# V1c_pcb.net
KiCad netlist of a schematic drawn in EAGLE
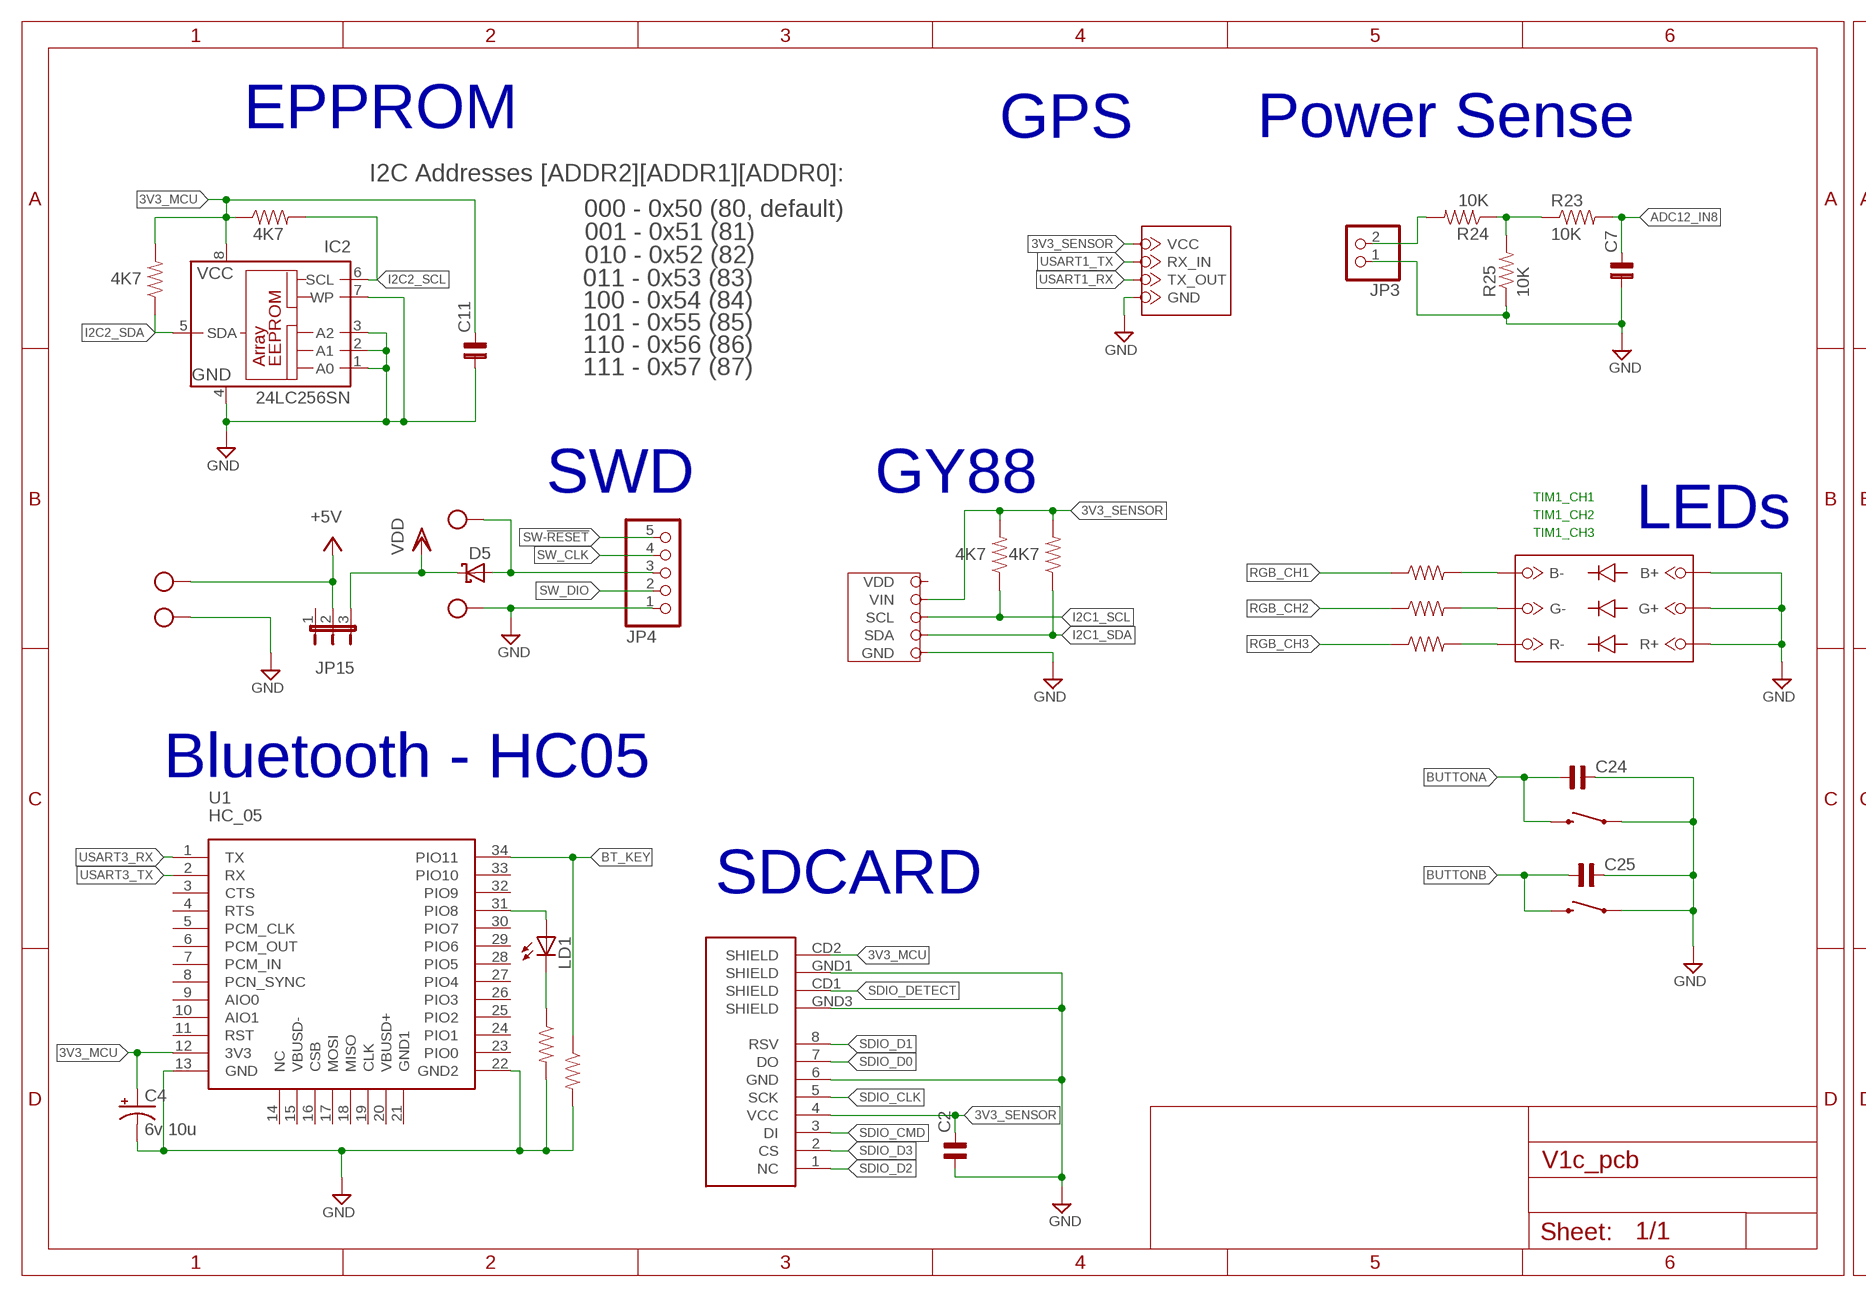
[diagram p0: schematic, sheet 1, part 1 of 2]
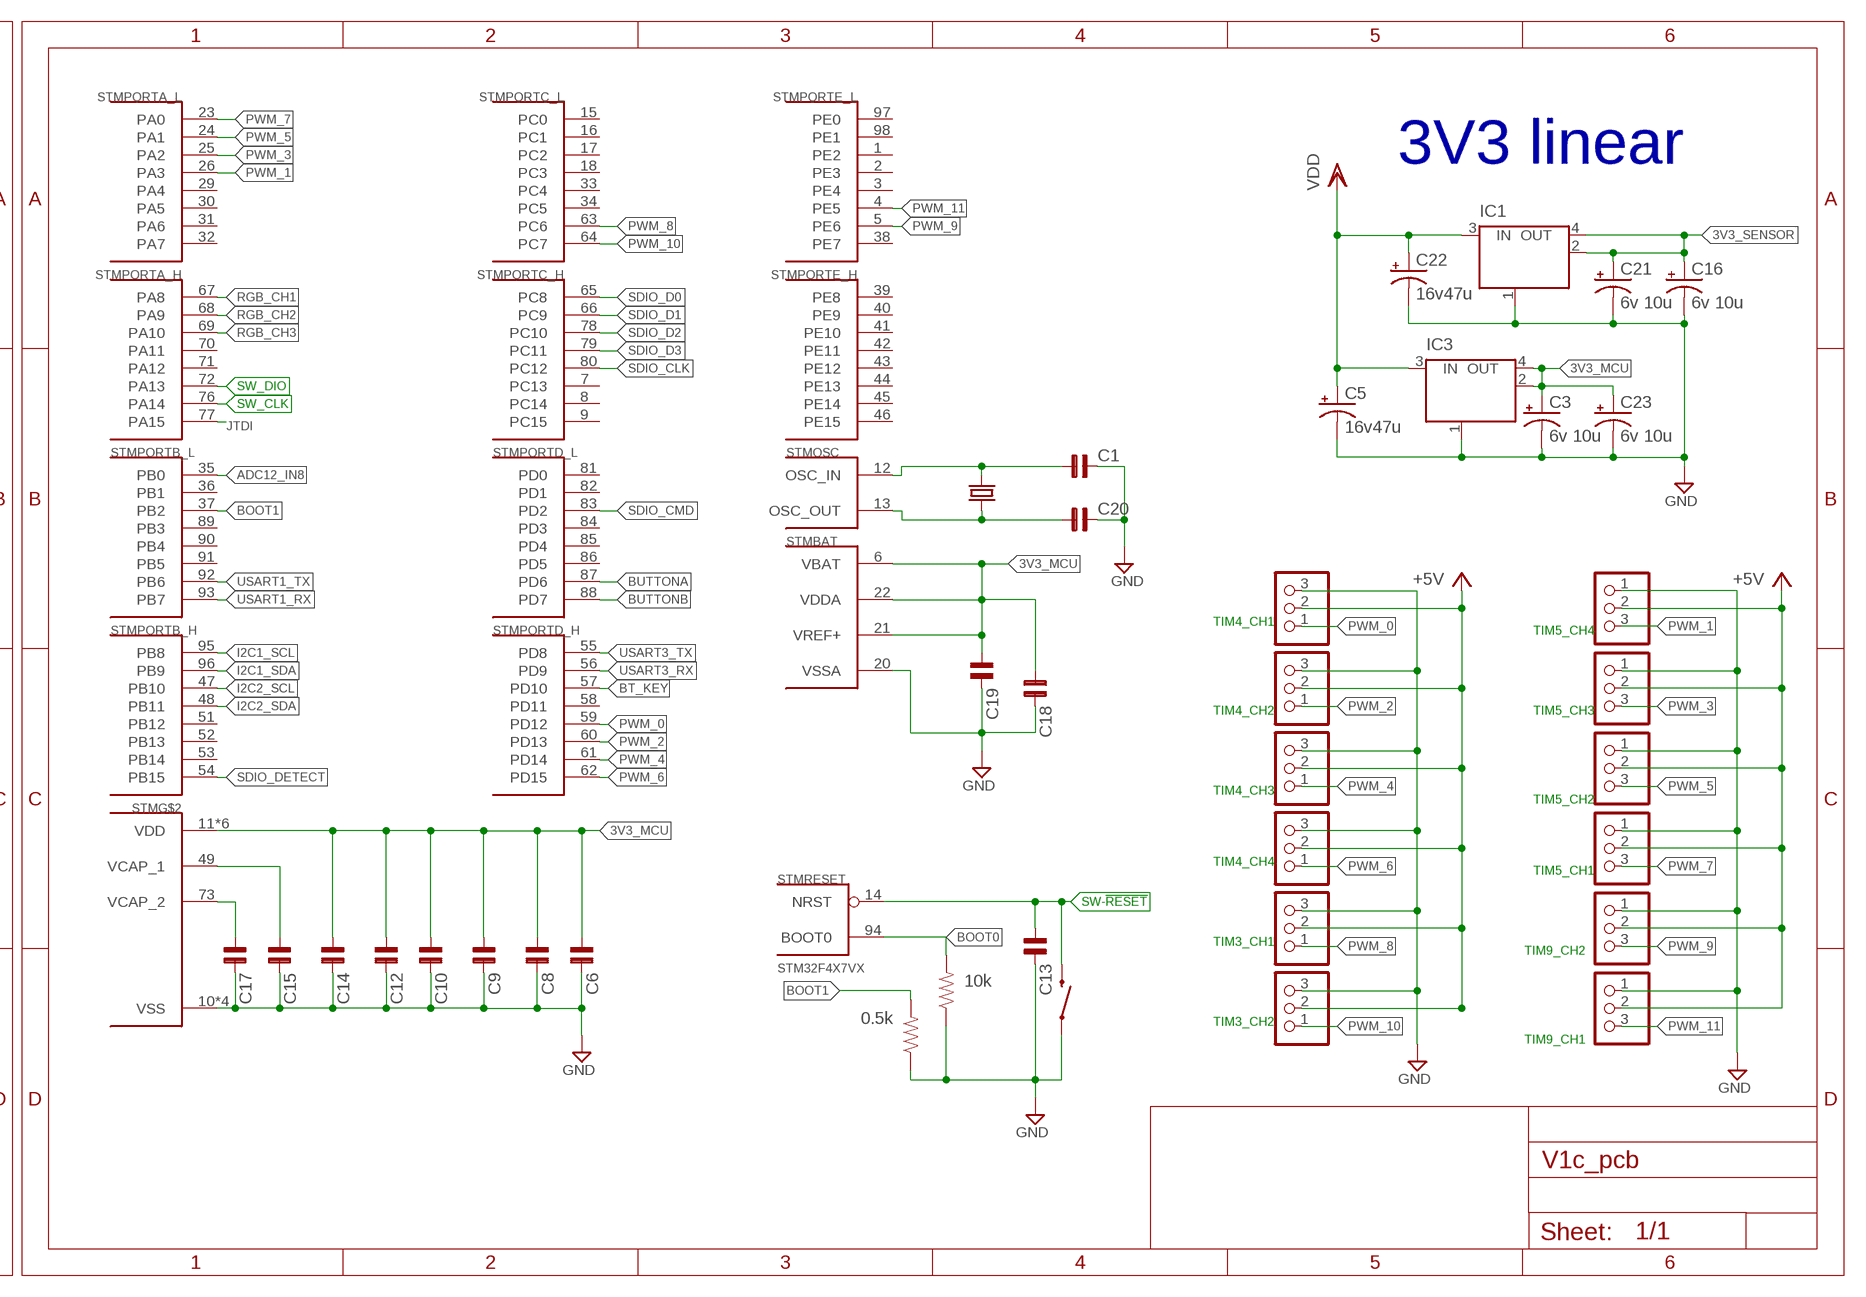
[diagram p1: schematic, sheet 1, part 2 of 2]

(export (version "E")
  (design (tool "Eeschema 10.0.6"))
  (components
    (comp (ref "C1")
      (value "C-NP-SMD-0603")
      (footprint "eagle-import:C-0603")
      (libsource (lib "eagle-import") (part "C-NP-SMD-0603"))
    )
    (comp (ref "C2")
      (value "C-NP-SMD-0603")
      (footprint "eagle-import:C-0603")
      (libsource (lib "eagle-import") (part "C-NP-SMD-0603"))
    )
    (comp (ref "C3")
      (value "6v 10u")
      (footprint "eagle-import:SMC_A")
      (libsource (lib "eagle-import") (part "CPOL-USSMCA"))
    )
    (comp (ref "C4")
      (value "6v 10u")
      (footprint "eagle-import:SMC_A")
      (libsource (lib "eagle-import") (part "CPOL-USSMCA"))
    )
    (comp (ref "C5")
      (value "16v47u")
      (footprint "eagle-import:SMC_C")
      (libsource (lib "eagle-import") (part "CPOL-USSMCC"))
    )
    (comp (ref "C6")
      (value "C-NP-SMD-0603")
      (footprint "eagle-import:C-0603")
      (libsource (lib "eagle-import") (part "C-NP-SMD-0603"))
    )
    (comp (ref "C7")
      (value "C-NP-SMD-0603")
      (footprint "eagle-import:C-0603")
      (libsource (lib "eagle-import") (part "C-NP-SMD-0603"))
    )
    (comp (ref "C8")
      (value "C-NP-SMD-0603")
      (footprint "eagle-import:C-0603")
      (libsource (lib "eagle-import") (part "C-NP-SMD-0603"))
    )
    (comp (ref "C9")
      (value "C-NP-SMD-0603")
      (footprint "eagle-import:C-0603")
      (libsource (lib "eagle-import") (part "C-NP-SMD-0603"))
    )
    (comp (ref "C10")
      (value "C-NP-SMD-0603")
      (footprint "eagle-import:C-0603")
      (libsource (lib "eagle-import") (part "C-NP-SMD-0603"))
    )
    (comp (ref "C11")
      (value "C-NP-SMD-0603")
      (footprint "eagle-import:C-0603")
      (libsource (lib "eagle-import") (part "C-NP-SMD-0603"))
    )
    (comp (ref "C12")
      (value "C-NP-SMD-0603")
      (footprint "eagle-import:C-0603")
      (libsource (lib "eagle-import") (part "C-NP-SMD-0603"))
    )
    (comp (ref "C13")
      (value "C-NP-SMD-0603")
      (footprint "eagle-import:C-0603")
      (libsource (lib "eagle-import") (part "C-NP-SMD-0603"))
    )
    (comp (ref "C14")
      (value "C-NP-SMD-0603")
      (footprint "eagle-import:C-0603")
      (libsource (lib "eagle-import") (part "C-NP-SMD-0603"))
    )
    (comp (ref "C15")
      (value "C-NP-SMD-0603")
      (footprint "eagle-import:C-0603")
      (libsource (lib "eagle-import") (part "C-NP-SMD-0603"))
    )
    (comp (ref "C16")
      (value "6v 10u")
      (footprint "eagle-import:SMC_A")
      (libsource (lib "eagle-import") (part "CPOL-USSMCA"))
    )
    (comp (ref "C17")
      (value "C-NP-SMD-0603")
      (footprint "eagle-import:C-0603")
      (libsource (lib "eagle-import") (part "C-NP-SMD-0603"))
    )
    (comp (ref "C18")
      (value "C-NP-SMD-0603")
      (footprint "eagle-import:C-0603")
      (libsource (lib "eagle-import") (part "C-NP-SMD-0603"))
    )
    (comp (ref "C19")
      (value "C-NP-SMD-0603")
      (footprint "eagle-import:C-0603")
      (libsource (lib "eagle-import") (part "C-NP-SMD-0603"))
    )
    (comp (ref "C20")
      (value "C-NP-SMD-0603")
      (footprint "eagle-import:C-0603")
      (libsource (lib "eagle-import") (part "C-NP-SMD-0603"))
    )
    (comp (ref "C21")
      (value "6v 10u")
      (footprint "eagle-import:SMC_A")
      (libsource (lib "eagle-import") (part "CPOL-USSMCA"))
    )
    (comp (ref "C22")
      (value "16v47u")
      (footprint "eagle-import:SMC_C")
      (libsource (lib "eagle-import") (part "CPOL-USSMCC"))
    )
    (comp (ref "C23")
      (value "6v 10u")
      (footprint "eagle-import:SMC_A")
      (libsource (lib "eagle-import") (part "CPOL-USSMCA"))
    )
    (comp (ref "C24")
      (value "C-NP-SMD-0603")
      (footprint "eagle-import:C-0603")
      (libsource (lib "eagle-import") (part "C-NP-SMD-0603"))
    )
    (comp (ref "C25")
      (value "C-NP-SMD-0603")
      (footprint "eagle-import:C-0603")
      (libsource (lib "eagle-import") (part "C-NP-SMD-0603"))
    )
    (comp (ref "D5")
      (value "MBRS330T3")
      (footprint "eagle-import:SMC")
      (libsource (lib "eagle-import") (part "MBRS30T33"))
    )
    (comp (ref "IC1")
      (value "LINEAR_MC33269ST-3.3T3")
      (footprint "eagle-import:LINEAR_SOT223")
      (libsource (lib "eagle-import") (part "LINEAR_MC33269ST-3.3T3"))
    )
    (comp (ref "IC2")
      (value "24LC256SN")
      (footprint "eagle-import:SO-08")
      (fields (field (name "MF") "MICROCHIP") (field (name "MPN") "24LC256-I/SN"))
      (libsource (lib "eagle-import") (part "24SNLC256"))
    )
    (comp (ref "IC3")
      (value "LINEAR_MC33269ST-3.3T3")
      (footprint "eagle-import:LINEAR_SOT223")
      (libsource (lib "eagle-import") (part "LINEAR_MC33269ST-3.3T3"))
    )
    (comp (ref "JP1")
      (value "PINHD-1X3_2.54-90°")
      (footprint "eagle-import:1X03_90")
      (libsource (lib "eagle-import") (part "PINHD-1X3_2.54-90°"))
    )
    (comp (ref "JP2")
      (value "PINHD-1X3_2.54-90°")
      (footprint "eagle-import:1X03_90")
      (libsource (lib "eagle-import") (part "PINHD-1X3_2.54-90°"))
    )
    (comp (ref "JP3")
      (value "PINHD-1X2")
      (footprint "eagle-import:1X02")
      (libsource (lib "eagle-import") (part "PINHD-1X2"))
    )
    (comp (ref "JP4")
      (value "PINHD-1X5_2.54-90°")
      (footprint "eagle-import:1X05_90")
      (libsource (lib "eagle-import") (part "PINHD-1X5_2.54-90°"))
    )
    (comp (ref "JP5")
      (value "PINHD-1X3_2.54-90°")
      (footprint "eagle-import:1X03_90")
      (libsource (lib "eagle-import") (part "PINHD-1X3_2.54-90°"))
    )
    (comp (ref "JP6")
      (value "PINHD-1X3_2.54-90°")
      (footprint "eagle-import:1X03_90")
      (libsource (lib "eagle-import") (part "PINHD-1X3_2.54-90°"))
    )
    (comp (ref "JP7")
      (value "PINHD-1X3_2.54-90°")
      (footprint "eagle-import:1X03_90")
      (libsource (lib "eagle-import") (part "PINHD-1X3_2.54-90°"))
    )
    (comp (ref "JP8")
      (value "PINHD-1X3_2.54-90°")
      (footprint "eagle-import:1X03_90")
      (libsource (lib "eagle-import") (part "PINHD-1X3_2.54-90°"))
    )
    (comp (ref "JP9")
      (value "PINHD-1X3_2.54-90°")
      (footprint "eagle-import:1X03_90")
      (libsource (lib "eagle-import") (part "PINHD-1X3_2.54-90°"))
    )
    (comp (ref "JP10")
      (value "PINHD-1X3_2.54-90°")
      (footprint "eagle-import:1X03_90")
      (libsource (lib "eagle-import") (part "PINHD-1X3_2.54-90°"))
    )
    (comp (ref "JP11")
      (value "PINHD-1X3_2.54-90°")
      (footprint "eagle-import:1X03_90")
      (libsource (lib "eagle-import") (part "PINHD-1X3_2.54-90°"))
    )
    (comp (ref "JP12")
      (value "PINHD-1X3_2.54-90°")
      (footprint "eagle-import:1X03_90")
      (libsource (lib "eagle-import") (part "PINHD-1X3_2.54-90°"))
    )
    (comp (ref "JP13")
      (value "PINHD-1X3_2.54-90°")
      (footprint "eagle-import:1X03_90")
      (libsource (lib "eagle-import") (part "PINHD-1X3_2.54-90°"))
    )
    (comp (ref "JP14")
      (value "PINHD-1X3_2.54-90°")
      (footprint "eagle-import:1X03_90")
      (libsource (lib "eagle-import") (part "PINHD-1X3_2.54-90°"))
    )
    (comp (ref "JP15")
      (value "JP2E")
      (footprint "eagle-import:JP2")
      (libsource (lib "eagle-import") (part "JP2E"))
    )
    (comp (ref "LD1")
      (value "LEDCHIPLED_0805")
      (footprint "eagle-import:CHIPLED_0805")
      (libsource (lib "eagle-import") (part "LEDCHIPLED_0805"))
    )
    (comp (ref "R1")
      (value "4K7")
      (footprint "eagle-import:SPARKFUN_0603-RES")
      (libsource (lib "eagle-import") (part "SPARKFUN_RESISTOR0603-RES"))
    )
    (comp (ref "R2")
      (value "10K")
      (footprint "eagle-import:SPARKFUN_0603-RES")
      (libsource (lib "eagle-import") (part "SPARKFUN_RESISTOR0603-RES"))
    )
    (comp (ref "R3")
      (value "10K")
      (footprint "eagle-import:SPARKFUN_0603-RES")
      (libsource (lib "eagle-import") (part "SPARKFUN_RESISTOR0603-RES"))
    )
    (comp (ref "R4")
      (value "4K7")
      (footprint "eagle-import:SPARKFUN_0603-RES")
      (libsource (lib "eagle-import") (part "SPARKFUN_RESISTOR0603-RES"))
    )
    (comp (ref "R5")
      (value "10K")
      (footprint "eagle-import:SPARKFUN_0603-RES")
      (libsource (lib "eagle-import") (part "SPARKFUN_RESISTOR0603-RES"))
    )
    (comp (ref "R6")
      (value "10K")
      (footprint "eagle-import:SPARKFUN_0603-RES")
      (libsource (lib "eagle-import") (part "SPARKFUN_RESISTOR0603-RES"))
    )
    (comp (ref "R7")
      (value "10k")
      (footprint "eagle-import:SPARKFUN_0603-RES")
      (libsource (lib "eagle-import") (part "SPARKFUN_RESISTOR0603-RES"))
    )
    (comp (ref "R8")
      (value "0.5k")
      (footprint "eagle-import:SPARKFUN_0603-RES")
      (libsource (lib "eagle-import") (part "SPARKFUN_RESISTOR0603-RES"))
    )
    (comp (ref "R9")
      (value "10K")
      (footprint "eagle-import:SPARKFUN_0603-RES")
      (libsource (lib "eagle-import") (part "SPARKFUN_RESISTOR0603-RES"))
    )
    (comp (ref "R15")
      (value "4K7")
      (footprint "eagle-import:SPARKFUN_0603-RES")
      (libsource (lib "eagle-import") (part "SPARKFUN_RESISTOR0603-RES"))
    )
    (comp (ref "R16")
      (value "4K7")
      (footprint "eagle-import:SPARKFUN_0603-RES")
      (libsource (lib "eagle-import") (part "SPARKFUN_RESISTOR0603-RES"))
    )
    (comp (ref "R23")
      (value "10K")
      (footprint "eagle-import:SPARKFUN_0603-RES")
      (libsource (lib "eagle-import") (part "SPARKFUN_RESISTOR0603-RES"))
    )
    (comp (ref "R24")
      (value "10K")
      (footprint "eagle-import:SPARKFUN_0603-RES")
      (libsource (lib "eagle-import") (part "SPARKFUN_RESISTOR0603-RES"))
    )
    (comp (ref "R25")
      (value "10K")
      (footprint "eagle-import:SPARKFUN_0603-RES")
      (libsource (lib "eagle-import") (part "SPARKFUN_RESISTOR0603-RES"))
    )
    (comp (ref "S1")
      (value "RESET")
      (footprint "eagle-import:TACTILE-SWITCH-1101NE")
      (fields (field (name "PARTNO") "EVQ-P7J01P"))
      (libsource (lib "eagle-import") (part "SWITCH-MOMENTARY-2-SMD-1101NE"))
    )
    (comp (ref "S2")
      (value "RESET")
      (footprint "eagle-import:TACTILE-SWITCH-1101NE")
      (fields (field (name "PARTNO") "EVQ-P7J01P"))
      (libsource (lib "eagle-import") (part "SWITCH-MOMENTARY-2-SMD-1101NE"))
    )
    (comp (ref "S3")
      (value "RESET")
      (footprint "eagle-import:TACTILE-SWITCH-1101NE")
      (fields (field (name "PARTNO") "EVQ-P7J01P"))
      (libsource (lib "eagle-import") (part "SWITCH-MOMENTARY-2-SMD-1101NE"))
    )
    (comp (ref "SDCARD2")
      (value "microSD Socket")
      (footprint "eagle-import:MICRO-SD-SOCKET-PP")
      (libsource (lib "eagle-import") (part "USD-SOCKETNEW"))
    )
    (comp (ref "STM")
      (value "STM32F4X7VX")
      (footprint "eagle-import:TQFP100")
      (fields (field (name "PARTNO") "STM32F427VI"))
      (libsource (lib "eagle-import") (part "STM32F4X7VX"))
    )
    (comp (ref "U$1")
      (value "GY-88")
      (footprint "eagle-import:BREAKOUT")
      (libsource (lib "eagle-import") (part "GY-88"))
    )
    (comp (ref "U$10")
      (value "GPS_MODULE")
      (footprint "eagle-import:23X30")
      (libsource (lib "eagle-import") (part "GPS_MODULE"))
    )
    (comp (ref "U$12")
      (value "RGB_LED")
      (footprint "eagle-import:SMD")
      (libsource (lib "eagle-import") (part "RGB_LED"))
    )
    (comp (ref "U1")
      (value "HC_05")
      (footprint "eagle-import:BLUETOOTH_SMD")
      (libsource (lib "eagle-import") (part "HC_05"))
    )
    (comp (ref "X1")
      (value "MKDSN1,5/2-5,08")
      (footprint "eagle-import:MKDSN1,5_2-5,08")
      (fields (field (name "MPN") "MKDSN 1,5/2-5.08"))
      (libsource (lib "eagle-import") (part "MKDSN1,5/2-5,08"))
    )
    (comp (ref "X2")
      (value "MKDSN1,5/2-5,08")
      (footprint "eagle-import:MKDSN1,5_2-5,08")
      (fields (field (name "MPN") "MKDSN 1,5/2-5.08"))
      (libsource (lib "eagle-import") (part "MKDSN1,5/2-5,08"))
    )
    (comp (ref "Y1")
      (value "CRYSTALHC49US")
      (footprint "eagle-import:HC49US")
      (libsource (lib "eagle-import") (part "CRYSTALHC49US"))
    )
  )
  (nets
    (net (code "1") (name "+5V") (class "Default")
      (node (ref "JP1") (pin "2") (pinfunction "2_2") (pintype "passive"))
      (node (ref "JP10") (pin "2") (pinfunction "2_2") (pintype "passive"))
      (node (ref "JP11") (pin "2") (pinfunction "2_2") (pintype "passive"))
      (node (ref "JP12") (pin "2") (pinfunction "2_2") (pintype "passive"))
      (node (ref "JP13") (pin "2") (pinfunction "2_2") (pintype "passive"))
      (node (ref "JP14") (pin "2") (pinfunction "2_2") (pintype "passive"))
      (node (ref "JP15") (pin "2") (pinfunction "2_2") (pintype "passive"))
      (node (ref "JP2") (pin "2") (pinfunction "2_2") (pintype "passive"))
      (node (ref "JP5") (pin "2") (pinfunction "2_2") (pintype "passive"))
      (node (ref "JP6") (pin "2") (pinfunction "2_2") (pintype "passive"))
      (node (ref "JP7") (pin "2") (pinfunction "2_2") (pintype "passive"))
      (node (ref "JP8") (pin "2") (pinfunction "2_2") (pintype "passive"))
      (node (ref "JP9") (pin "2") (pinfunction "2_2") (pintype "passive"))
      (node (ref "X2") (pin "2") (pinfunction "KL_2") (pintype "passive"))
    )
    (net (code "2") (name "/JTDI") (class "Default")
      (node (ref "STM") (pin "77") (pinfunction "PA15_77") (pintype "bidirectional"))
    )
    (net (code "3") (name "/SW-~{RESET}") (class "Default")
      (node (ref "C13") (pin "1") (pinfunction "1_1") (pintype "passive"))
      (node (ref "JP4") (pin "5") (pinfunction "5_5") (pintype "passive"))
      (node (ref "S1") (pin "P$2") (pinfunction "2_P$2") (pintype "passive"))
      (node (ref "STM") (pin "14") (pinfunction "NRST_14") (pintype "input"))
    )
    (net (code "4") (name "3V3_MCU") (class "Default")
      (node (ref "C10") (pin "1") (pinfunction "1_1") (pintype "passive"))
      (node (ref "C11") (pin "2") (pinfunction "2_2") (pintype "passive"))
      (node (ref "C12") (pin "1") (pinfunction "1_1") (pintype "passive"))
      (node (ref "C14") (pin "1") (pinfunction "1_1") (pintype "passive"))
      (node (ref "C18") (pin "1") (pinfunction "1_1") (pintype "passive"))
      (node (ref "C19") (pin "1") (pinfunction "1_1") (pintype "passive"))
      (node (ref "C23") (pin "+") (pinfunction "+_+") (pintype "passive"))
      (node (ref "C3") (pin "+") (pinfunction "+_+") (pintype "passive"))
      (node (ref "C4") (pin "+") (pinfunction "+_+") (pintype "passive"))
      (node (ref "C6") (pin "1") (pinfunction "1_1") (pintype "passive"))
      (node (ref "C8") (pin "1") (pinfunction "1_1") (pintype "passive"))
      (node (ref "C9") (pin "1") (pinfunction "1_1") (pintype "passive"))
      (node (ref "IC2") (pin "8") (pinfunction "VCC_8") (pintype "power_in"))
      (node (ref "IC3") (pin "2") (pinfunction "OUT_2") (pintype "passive"))
      (node (ref "IC3") (pin "4") (pinfunction "OUT_4") (pintype "passive"))
      (node (ref "R15") (pin "1") (pinfunction "1_1") (pintype "passive"))
      (node (ref "R16") (pin "2") (pinfunction "2_2") (pintype "passive"))
      (node (ref "SDCARD2") (pin "CD2") (pinfunction "SHIELD_CD2") (pintype "bidirectional"))
      (node (ref "STM") (pin "100") (pinfunction "VDD_100") (pintype "power_in"))
      (node (ref "STM") (pin "11") (pinfunction "VDD_11") (pintype "power_in"))
      (node (ref "STM") (pin "19") (pinfunction "VDD_19") (pintype "power_in"))
      (node (ref "STM") (pin "21") (pinfunction "VREF+_21") (pintype "input"))
      (node (ref "STM") (pin "22") (pinfunction "VDDA_22") (pintype "power_in"))
      (node (ref "STM") (pin "28") (pinfunction "VDD_28") (pintype "power_in"))
      (node (ref "STM") (pin "50") (pinfunction "VDD_50") (pintype "power_in"))
      (node (ref "STM") (pin "6") (pinfunction "VBAT_6") (pintype "power_in"))
      (node (ref "STM") (pin "75") (pinfunction "VDD_75") (pintype "power_in"))
      (node (ref "U1") (pin "12") (pinfunction "3V3_12") (pintype "bidirectional"))
    )
    (net (code "5") (name "3V3_SENSOR") (class "Default")
      (node (ref "C16") (pin "+") (pinfunction "+_+") (pintype "passive"))
      (node (ref "C2") (pin "2") (pinfunction "2_2") (pintype "passive"))
      (node (ref "C21") (pin "+") (pinfunction "+_+") (pintype "passive"))
      (node (ref "IC1") (pin "2") (pinfunction "OUT_2") (pintype "passive"))
      (node (ref "IC1") (pin "4") (pinfunction "OUT_4") (pintype "passive"))
      (node (ref "R1") (pin "2") (pinfunction "2_2") (pintype "passive"))
      (node (ref "R4") (pin "2") (pinfunction "2_2") (pintype "passive"))
      (node (ref "SDCARD2") (pin "4") (pinfunction "VCC_4") (pintype "bidirectional"))
      (node (ref "U$1") (pin "2") (pinfunction "VIN_2") (pintype "bidirectional"))
      (node (ref "U$10") (pin "4") (pinfunction "VCC_4") (pintype "bidirectional"))
    )
    (net (code "6") (name "ADC12_IN8") (class "Default")
      (node (ref "C7") (pin "2") (pinfunction "2_2") (pintype "passive"))
      (node (ref "R23") (pin "2") (pinfunction "2_2") (pintype "passive"))
      (node (ref "STM") (pin "35") (pinfunction "PB0_35") (pintype "bidirectional"))
    )
    (net (code "7") (name "BOOT0") (class "Default")
      (node (ref "R7") (pin "2") (pinfunction "2_2") (pintype "passive"))
      (node (ref "STM") (pin "94") (pinfunction "BOOT0_94") (pintype "input"))
    )
    (net (code "8") (name "BOOT1") (class "Default")
      (node (ref "R8") (pin "2") (pinfunction "2_2") (pintype "passive"))
      (node (ref "STM") (pin "37") (pinfunction "PB2_37") (pintype "bidirectional"))
    )
    (net (code "9") (name "BT_KEY") (class "Default")
      (node (ref "R5") (pin "1") (pinfunction "1_1") (pintype "passive"))
      (node (ref "STM") (pin "57") (pinfunction "PD10_57") (pintype "bidirectional"))
      (node (ref "U1") (pin "34") (pinfunction "PIO11_34") (pintype "bidirectional"))
    )
    (net (code "10") (name "BUTTONA") (class "Default")
      (node (ref "C24") (pin "1") (pinfunction "1_1") (pintype "passive"))
      (node (ref "S3") (pin "P$2") (pinfunction "2_P$2") (pintype "passive"))
      (node (ref "STM") (pin "87") (pinfunction "PD6_87") (pintype "bidirectional"))
    )
    (net (code "11") (name "BUTTONB") (class "Default")
      (node (ref "C25") (pin "1") (pinfunction "1_1") (pintype "passive"))
      (node (ref "S2") (pin "P$2") (pinfunction "2_P$2") (pintype "passive"))
      (node (ref "STM") (pin "88") (pinfunction "PD7_88") (pintype "bidirectional"))
    )
    (net (code "12") (name "GND") (class "Default")
      (node (ref "C1") (pin "2") (pinfunction "2_2") (pintype "passive"))
      (node (ref "C10") (pin "2") (pinfunction "2_2") (pintype "passive"))
      (node (ref "C11") (pin "1") (pinfunction "1_1") (pintype "passive"))
      (node (ref "C12") (pin "2") (pinfunction "2_2") (pintype "passive"))
      (node (ref "C13") (pin "2") (pinfunction "2_2") (pintype "passive"))
      (node (ref "C14") (pin "2") (pinfunction "2_2") (pintype "passive"))
      (node (ref "C15") (pin "2") (pinfunction "2_2") (pintype "passive"))
      (node (ref "C16") (pin "-") (pinfunction "-_-") (pintype "passive"))
      (node (ref "C17") (pin "2") (pinfunction "2_2") (pintype "passive"))
      (node (ref "C18") (pin "2") (pinfunction "2_2") (pintype "passive"))
      (node (ref "C19") (pin "2") (pinfunction "2_2") (pintype "passive"))
      (node (ref "C2") (pin "1") (pinfunction "1_1") (pintype "passive"))
      (node (ref "C20") (pin "2") (pinfunction "2_2") (pintype "passive"))
      (node (ref "C21") (pin "-") (pinfunction "-_-") (pintype "passive"))
      (node (ref "C22") (pin "-") (pinfunction "-_-") (pintype "passive"))
      (node (ref "C23") (pin "-") (pinfunction "-_-") (pintype "passive"))
      (node (ref "C24") (pin "2") (pinfunction "2_2") (pintype "passive"))
      (node (ref "C25") (pin "2") (pinfunction "2_2") (pintype "passive"))
      (node (ref "C3") (pin "-") (pinfunction "-_-") (pintype "passive"))
      (node (ref "C4") (pin "-") (pinfunction "-_-") (pintype "passive"))
      (node (ref "C5") (pin "-") (pinfunction "-_-") (pintype "passive"))
      (node (ref "C6") (pin "2") (pinfunction "2_2") (pintype "passive"))
      (node (ref "C7") (pin "1") (pinfunction "1_1") (pintype "passive"))
      (node (ref "C8") (pin "2") (pinfunction "2_2") (pintype "passive"))
      (node (ref "C9") (pin "2") (pinfunction "2_2") (pintype "passive"))
      (node (ref "IC1") (pin "1") (pinfunction "GND/ADJ_1") (pintype "input"))
      (node (ref "IC2") (pin "1") (pinfunction "A0_1") (pintype "input"))
      (node (ref "IC2") (pin "2") (pinfunction "A1_2") (pintype "input"))
      (node (ref "IC2") (pin "3") (pinfunction "A2_3") (pintype "input"))
      (node (ref "IC2") (pin "4") (pinfunction "GND_4") (pintype "power_in"))
      (node (ref "IC2") (pin "7") (pinfunction "WP_7") (pintype "input"))
      (node (ref "IC3") (pin "1") (pinfunction "GND/ADJ_1") (pintype "input"))
      (node (ref "JP1") (pin "1") (pinfunction "1_1") (pintype "passive"))
      (node (ref "JP10") (pin "3") (pinfunction "3_3") (pintype "passive"))
      (node (ref "JP11") (pin "1") (pinfunction "1_1") (pintype "passive"))
      (node (ref "JP12") (pin "3") (pinfunction "3_3") (pintype "passive"))
      (node (ref "JP13") (pin "3") (pinfunction "3_3") (pintype "passive"))
      (node (ref "JP14") (pin "3") (pinfunction "3_3") (pintype "passive"))
      (node (ref "JP2") (pin "1") (pinfunction "1_1") (pintype "passive"))
      (node (ref "JP3") (pin "1") (pinfunction "1_1") (pintype "passive"))
      (node (ref "JP4") (pin "1") (pinfunction "1_1") (pintype "passive"))
      (node (ref "JP5") (pin "1") (pinfunction "1_1") (pintype "passive"))
      (node (ref "JP6") (pin "1") (pinfunction "1_1") (pintype "passive"))
      (node (ref "JP7") (pin "3") (pinfunction "3_3") (pintype "passive"))
      (node (ref "JP8") (pin "1") (pinfunction "1_1") (pintype "passive"))
      (node (ref "JP9") (pin "3") (pinfunction "3_3") (pintype "passive"))
      (node (ref "R25") (pin "1") (pinfunction "1_1") (pintype "passive"))
      (node (ref "R5") (pin "2") (pinfunction "2_2") (pintype "passive"))
      (node (ref "R7") (pin "1") (pinfunction "1_1") (pintype "passive"))
      (node (ref "R8") (pin "1") (pinfunction "1_1") (pintype "passive"))
      (node (ref "R9") (pin "2") (pinfunction "2_2") (pintype "passive"))
      (node (ref "S1") (pin "P$1") (pinfunction "1_P$1") (pintype "passive"))
      (node (ref "S2") (pin "P$1") (pinfunction "1_P$1") (pintype "passive"))
      (node (ref "S3") (pin "P$1") (pinfunction "1_P$1") (pintype "passive"))
      (node (ref "SDCARD2") (pin "6") (pinfunction "GND_6") (pintype "bidirectional"))
      (node (ref "SDCARD2") (pin "GND1") (pinfunction "SHIELD_GND1") (pintype "bidirectional"))
      (node (ref "SDCARD2") (pin "GND3") (pinfunction "SHIELD_GND3") (pintype "bidirectional"))
      (node (ref "STM") (pin "10") (pinfunction "VSS_10") (pintype "power_in"))
      (node (ref "STM") (pin "20") (pinfunction "VSSA_20") (pintype "power_in"))
      (node (ref "STM") (pin "27") (pinfunction "VSS_27") (pintype "power_in"))
      (node (ref "STM") (pin "74") (pinfunction "VSS_74") (pintype "power_in"))
      (node (ref "STM") (pin "99") (pinfunction "VSS_99") (pintype "power_in"))
      (node (ref "U$1") (pin "3") (pinfunction "GND_3") (pintype "bidirectional"))
      (node (ref "U$10") (pin "1") (pinfunction "GND_1") (pintype "bidirectional"))
      (node (ref "U$12") (pin "B+") (pinfunction "B+_B+") (pintype "bidirectional"))
      (node (ref "U$12") (pin "G+") (pinfunction "G+_G+") (pintype "bidirectional"))
      (node (ref "U$12") (pin "R+") (pinfunction "R+_R+") (pintype "bidirectional"))
      (node (ref "U1") (pin "13") (pinfunction "GND_13") (pintype "bidirectional"))
      (node (ref "U1") (pin "22") (pinfunction "GND2_22") (pintype "bidirectional"))
      (node (ref "X1") (pin "2") (pinfunction "KL_2") (pintype "passive"))
      (node (ref "X2") (pin "1") (pinfunction "KL_1") (pintype "passive"))
    )
    (net (code "13") (name "I2C1_SCL") (class "Default")
      (node (ref "R1") (pin "1") (pinfunction "1_1") (pintype "passive"))
      (node (ref "STM") (pin "95") (pinfunction "PB8_95") (pintype "bidirectional"))
      (node (ref "U$1") (pin "4") (pinfunction "SCL_4") (pintype "bidirectional"))
    )
    (net (code "14") (name "I2C1_SDA") (class "Default")
      (node (ref "R4") (pin "1") (pinfunction "1_1") (pintype "passive"))
      (node (ref "STM") (pin "96") (pinfunction "PB9_96") (pintype "bidirectional"))
      (node (ref "U$1") (pin "5") (pinfunction "SDA_5") (pintype "bidirectional"))
    )
    (net (code "15") (name "I2C2_SCL") (class "Default")
      (node (ref "IC2") (pin "6") (pinfunction "SCL_6") (pintype "input"))
      (node (ref "R15") (pin "2") (pinfunction "2_2") (pintype "passive"))
      (node (ref "STM") (pin "47") (pinfunction "PB10_47") (pintype "bidirectional"))
    )
    (net (code "16") (name "I2C2_SDA") (class "Default")
      (node (ref "IC2") (pin "5") (pinfunction "SDA_5") (pintype "bidirectional"))
      (node (ref "R16") (pin "1") (pinfunction "1_1") (pintype "passive"))
      (node (ref "STM") (pin "48") (pinfunction "PB11_48") (pintype "bidirectional"))
    )
    (net (code "17") (name "Net-(JP3-Pad2)") (class "Default")
      (node (ref "JP3") (pin "2") (pinfunction "2_2") (pintype "passive"))
      (node (ref "R24") (pin "2") (pinfunction "2_2") (pintype "passive"))
    )
    (net (code "18") (name "Net-(LD1-PadC)") (class "Default")
      (node (ref "LD1") (pin "C") (pinfunction "C_C") (pintype "passive"))
      (node (ref "R9") (pin "1") (pinfunction "1_1") (pintype "passive"))
    )
    (net (code "19") (name "Net-(R2-Pad2)") (class "Default")
      (node (ref "R2") (pin "2") (pinfunction "2_2") (pintype "passive"))
      (node (ref "U$12") (pin "B-") (pinfunction "B-_B-") (pintype "bidirectional"))
    )
    (net (code "20") (name "Net-(R3-Pad2)") (class "Default")
      (node (ref "R3") (pin "2") (pinfunction "2_2") (pintype "passive"))
      (node (ref "U$12") (pin "G-") (pinfunction "G-_G-") (pintype "bidirectional"))
    )
    (net (code "21") (name "Net-(R6-Pad2)") (class "Default")
      (node (ref "R6") (pin "2") (pinfunction "2_2") (pintype "passive"))
      (node (ref "U$12") (pin "R-") (pinfunction "R-_R-") (pintype "bidirectional"))
    )
    (net (code "22") (name "Net-(R23-Pad1)") (class "Default")
      (node (ref "R23") (pin "1") (pinfunction "1_1") (pintype "passive"))
      (node (ref "R24") (pin "1") (pinfunction "1_1") (pintype "passive"))
      (node (ref "R25") (pin "2") (pinfunction "2_2") (pintype "passive"))
    )
    (net (code "23") (name "Net-(STMB-VCAP_1)") (class "Default")
      (node (ref "C15") (pin "1") (pinfunction "1_1") (pintype "passive"))
      (node (ref "STM") (pin "49") (pinfunction "VCAP_1_49") (pintype "power_in"))
    )
    (net (code "24") (name "Net-(STMB-VCAP_2)") (class "Default")
      (node (ref "C17") (pin "1") (pinfunction "1_1") (pintype "passive"))
      (node (ref "STM") (pin "73") (pinfunction "VCAP_2_73") (pintype "power_in"))
    )
    (net (code "25") (name "Net-(STMC-OSC_IN)") (class "Default")
      (node (ref "C1") (pin "1") (pinfunction "1_1") (pintype "passive"))
      (node (ref "STM") (pin "12") (pinfunction "OSC_IN_12") (pintype "input"))
      (node (ref "Y1") (pin "2") (pinfunction "2_2") (pintype "passive"))
    )
    (net (code "26") (name "Net-(STMC-OSC_OUT)") (class "Default")
      (node (ref "C20") (pin "1") (pinfunction "1_1") (pintype "passive"))
      (node (ref "STM") (pin "13") (pinfunction "OSC_OUT_13") (pintype "output"))
      (node (ref "Y1") (pin "1") (pinfunction "1_1") (pintype "passive"))
    )
    (net (code "27") (name "Net-(U1-PIO8)") (class "Default")
      (node (ref "LD1") (pin "A") (pinfunction "A_A") (pintype "passive"))
      (node (ref "U1") (pin "31") (pinfunction "PIO8_31") (pintype "bidirectional"))
    )
    (net (code "28") (name "Net-(X1A-KL)") (class "Default")
      (node (ref "D5") (pin "A") (pinfunction "A_A") (pintype "passive"))
      (node (ref "JP4") (pin "3") (pinfunction "3_3") (pintype "passive"))
      (node (ref "X1") (pin "1") (pinfunction "KL_1") (pintype "passive"))
    )
    (net (code "29") (name "PWM_0") (class "Default")
      (node (ref "JP7") (pin "1") (pinfunction "1_1") (pintype "passive"))
      (node (ref "STM") (pin "59") (pinfunction "PD12_59") (pintype "bidirectional"))
    )
    (net (code "30") (name "PWM_1") (class "Default")
      (node (ref "JP6") (pin "3") (pinfunction "3_3") (pintype "passive"))
      (node (ref "STM") (pin "26") (pinfunction "PA3_26") (pintype "bidirectional"))
    )
    (net (code "31") (name "PWM_2") (class "Default")
      (node (ref "JP9") (pin "1") (pinfunction "1_1") (pintype "passive"))
      (node (ref "STM") (pin "60") (pinfunction "PD13_60") (pintype "bidirectional"))
    )
    (net (code "32") (name "PWM_3") (class "Default")
      (node (ref "JP11") (pin "3") (pinfunction "3_3") (pintype "passive"))
      (node (ref "STM") (pin "25") (pinfunction "PA2_25") (pintype "bidirectional"))
    )
    (net (code "33") (name "PWM_4") (class "Default")
      (node (ref "JP10") (pin "1") (pinfunction "1_1") (pintype "passive"))
      (node (ref "STM") (pin "61") (pinfunction "PD14_61") (pintype "bidirectional"))
    )
    (net (code "34") (name "PWM_5") (class "Default")
      (node (ref "JP5") (pin "3") (pinfunction "3_3") (pintype "passive"))
      (node (ref "STM") (pin "24") (pinfunction "PA1_24") (pintype "bidirectional"))
    )
    (net (code "35") (name "PWM_6") (class "Default")
      (node (ref "JP12") (pin "1") (pinfunction "1_1") (pintype "passive"))
      (node (ref "STM") (pin "62") (pinfunction "PD15_62") (pintype "bidirectional"))
    )
    (net (code "36") (name "PWM_7") (class "Default")
      (node (ref "JP1") (pin "3") (pinfunction "3_3") (pintype "passive"))
      (node (ref "STM") (pin "23") (pinfunction "PA0_23") (pintype "bidirectional"))
    )
    (net (code "37") (name "PWM_8") (class "Default")
      (node (ref "JP13") (pin "1") (pinfunction "1_1") (pintype "passive"))
      (node (ref "STM") (pin "63") (pinfunction "PC6_63") (pintype "bidirectional"))
    )
    (net (code "38") (name "PWM_9") (class "Default")
      (node (ref "JP8") (pin "3") (pinfunction "3_3") (pintype "passive"))
      (node (ref "STM") (pin "5") (pinfunction "PE6_5") (pintype "bidirectional"))
    )
    (net (code "39") (name "PWM_10") (class "Default")
      (node (ref "JP14") (pin "1") (pinfunction "1_1") (pintype "passive"))
      (node (ref "STM") (pin "64") (pinfunction "PC7_64") (pintype "bidirectional"))
    )
    (net (code "40") (name "PWM_11") (class "Default")
      (node (ref "JP2") (pin "3") (pinfunction "3_3") (pintype "passive"))
      (node (ref "STM") (pin "4") (pinfunction "PE5_4") (pintype "bidirectional"))
    )
    (net (code "41") (name "RGB_CH1") (class "Default")
      (node (ref "R2") (pin "1") (pinfunction "1_1") (pintype "passive"))
      (node (ref "STM") (pin "67") (pinfunction "PA8_67") (pintype "bidirectional"))
    )
    (net (code "42") (name "RGB_CH2") (class "Default")
      (node (ref "R3") (pin "1") (pinfunction "1_1") (pintype "passive"))
      (node (ref "STM") (pin "68") (pinfunction "PA9_68") (pintype "bidirectional"))
    )
    (net (code "43") (name "RGB_CH3") (class "Default")
      (node (ref "R6") (pin "1") (pinfunction "1_1") (pintype "passive"))
      (node (ref "STM") (pin "69") (pinfunction "PA10_69") (pintype "bidirectional"))
    )
    (net (code "44") (name "SDIO_CLK") (class "Default")
      (node (ref "SDCARD2") (pin "5") (pinfunction "SCK_5") (pintype "bidirectional"))
      (node (ref "STM") (pin "80") (pinfunction "PC12_80") (pintype "bidirectional"))
    )
    (net (code "45") (name "SDIO_CMD") (class "Default")
      (node (ref "SDCARD2") (pin "3") (pinfunction "DI_3") (pintype "bidirectional"))
      (node (ref "STM") (pin "83") (pinfunction "PD2_83") (pintype "bidirectional"))
    )
    (net (code "46") (name "SDIO_D0") (class "Default")
      (node (ref "SDCARD2") (pin "7") (pinfunction "DO_7") (pintype "bidirectional"))
      (node (ref "STM") (pin "65") (pinfunction "PC8_65") (pintype "bidirectional"))
    )
    (net (code "47") (name "SDIO_D1") (class "Default")
      (node (ref "SDCARD2") (pin "8") (pinfunction "RSV_8") (pintype "bidirectional"))
      (node (ref "STM") (pin "66") (pinfunction "PC9_66") (pintype "bidirectional"))
    )
    (net (code "48") (name "SDIO_D2") (class "Default")
      (node (ref "SDCARD2") (pin "1") (pinfunction "NC_1") (pintype "bidirectional"))
      (node (ref "STM") (pin "78") (pinfunction "PC10_78") (pintype "bidirectional"))
    )
    (net (code "49") (name "SDIO_D3") (class "Default")
      (node (ref "SDCARD2") (pin "2") (pinfunction "CS_2") (pintype "bidirectional"))
      (node (ref "STM") (pin "79") (pinfunction "PC11_79") (pintype "bidirectional"))
    )
    (net (code "50") (name "SDIO_DETECT") (class "Default")
      (node (ref "SDCARD2") (pin "CD1") (pinfunction "SHIELD_CD1") (pintype "bidirectional"))
      (node (ref "STM") (pin "54") (pinfunction "PB15_54") (pintype "bidirectional"))
    )
    (net (code "51") (name "SW_CLK") (class "Default")
      (node (ref "JP4") (pin "4") (pinfunction "4_4") (pintype "passive"))
      (node (ref "STM") (pin "76") (pinfunction "PA14_76") (pintype "bidirectional"))
    )
    (net (code "52") (name "SW_DIO") (class "Default")
      (node (ref "JP4") (pin "2") (pinfunction "2_2") (pintype "passive"))
      (node (ref "STM") (pin "72") (pinfunction "PA13_72") (pintype "bidirectional"))
    )
    (net (code "53") (name "USART1_RX") (class "Default")
      (node (ref "STM") (pin "93") (pinfunction "PB7_93") (pintype "bidirectional"))
      (node (ref "U$10") (pin "2") (pinfunction "TX_OUT_2") (pintype "bidirectional"))
    )
    (net (code "54") (name "USART1_TX") (class "Default")
      (node (ref "STM") (pin "92") (pinfunction "PB6_92") (pintype "bidirectional"))
      (node (ref "U$10") (pin "3") (pinfunction "RX_IN_3") (pintype "bidirectional"))
    )
    (net (code "55") (name "USART3_RX") (class "Default")
      (node (ref "STM") (pin "56") (pinfunction "PD9_56") (pintype "bidirectional"))
      (node (ref "U1") (pin "1") (pinfunction "TX_1") (pintype "bidirectional"))
    )
    (net (code "56") (name "USART3_TX") (class "Default")
      (node (ref "STM") (pin "55") (pinfunction "PD8_55") (pintype "bidirectional"))
      (node (ref "U1") (pin "2") (pinfunction "RX_2") (pintype "bidirectional"))
    )
    (net (code "57") (name "VDD") (class "Default")
      (node (ref "C22") (pin "+") (pinfunction "+_+") (pintype "passive"))
      (node (ref "C5") (pin "+") (pinfunction "+_+") (pintype "passive"))
      (node (ref "D5") (pin "C") (pinfunction "C_C") (pintype "passive"))
      (node (ref "IC1") (pin "3") (pinfunction "IN_3") (pintype "input"))
      (node (ref "IC3") (pin "3") (pinfunction "IN_3") (pintype "input"))
      (node (ref "JP15") (pin "3") (pinfunction "3_3") (pintype "passive"))
    )
    (net (code "58") (name "unconnected-(JP15-Pad1)") (class "Default")
      (node (ref "JP15") (pin "1") (pinfunction "1_1") (pintype "passive"))
    )
    (net (code "59") (name "unconnected-(STMD-PA11-Pad70)") (class "Default")
      (node (ref "STM") (pin "70") (pinfunction "PA11_70") (pintype "bidirectional"))
    )
    (net (code "60") (name "unconnected-(STMD-PA12-Pad71)") (class "Default")
      (node (ref "STM") (pin "71") (pinfunction "PA12_71") (pintype "bidirectional"))
    )
    (net (code "61") (name "unconnected-(STME-PA4-Pad29)") (class "Default")
      (node (ref "STM") (pin "29") (pinfunction "PA4_29") (pintype "bidirectional"))
    )
    (net (code "62") (name "unconnected-(STME-PA5-Pad30)") (class "Default")
      (node (ref "STM") (pin "30") (pinfunction "PA5_30") (pintype "bidirectional"))
    )
    (net (code "63") (name "unconnected-(STME-PA6-Pad31)") (class "Default")
      (node (ref "STM") (pin "31") (pinfunction "PA6_31") (pintype "bidirectional"))
    )
    (net (code "64") (name "unconnected-(STME-PA7-Pad32)") (class "Default")
      (node (ref "STM") (pin "32") (pinfunction "PA7_32") (pintype "bidirectional"))
    )
    (net (code "65") (name "unconnected-(STMF-PB12-Pad51)") (class "Default")
      (node (ref "STM") (pin "51") (pinfunction "PB12_51") (pintype "bidirectional"))
    )
    (net (code "66") (name "unconnected-(STMF-PB13-Pad52)") (class "Default")
      (node (ref "STM") (pin "52") (pinfunction "PB13_52") (pintype "bidirectional"))
    )
    (net (code "67") (name "unconnected-(STMF-PB14-Pad53)") (class "Default")
      (node (ref "STM") (pin "53") (pinfunction "PB14_53") (pintype "bidirectional"))
    )
    (net (code "68") (name "unconnected-(STMG-PB1-Pad36)") (class "Default")
      (node (ref "STM") (pin "36") (pinfunction "PB1_36") (pintype "bidirectional"))
    )
    (net (code "69") (name "unconnected-(STMG-PB3-Pad89)") (class "Default")
      (node (ref "STM") (pin "89") (pinfunction "PB3_89") (pintype "bidirectional"))
    )
    (net (code "70") (name "unconnected-(STMG-PB4-Pad90)") (class "Default")
      (node (ref "STM") (pin "90") (pinfunction "PB4_90") (pintype "bidirectional"))
    )
    (net (code "71") (name "unconnected-(STMG-PB5-Pad91)") (class "Default")
      (node (ref "STM") (pin "91") (pinfunction "PB5_91") (pintype "bidirectional"))
    )
    (net (code "72") (name "unconnected-(STMH-PC13-Pad7)") (class "Default")
      (node (ref "STM") (pin "7") (pinfunction "PC13_7") (pintype "bidirectional"))
    )
    (net (code "73") (name "unconnected-(STMH-PC14-Pad8)") (class "Default")
      (node (ref "STM") (pin "8") (pinfunction "PC14_8") (pintype "bidirectional"))
    )
    (net (code "74") (name "unconnected-(STMH-PC15-Pad9)") (class "Default")
      (node (ref "STM") (pin "9") (pinfunction "PC15_9") (pintype "bidirectional"))
    )
    (net (code "75") (name "unconnected-(STMI-PC0-Pad15)") (class "Default")
      (node (ref "STM") (pin "15") (pinfunction "PC0_15") (pintype "bidirectional"))
    )
    (net (code "76") (name "unconnected-(STMI-PC1-Pad16)") (class "Default")
      (node (ref "STM") (pin "16") (pinfunction "PC1_16") (pintype "bidirectional"))
    )
    (net (code "77") (name "unconnected-(STMI-PC2-Pad17)") (class "Default")
      (node (ref "STM") (pin "17") (pinfunction "PC2_17") (pintype "bidirectional"))
    )
    (net (code "78") (name "unconnected-(STMI-PC3-Pad18)") (class "Default")
      (node (ref "STM") (pin "18") (pinfunction "PC3_18") (pintype "bidirectional"))
    )
    (net (code "79") (name "unconnected-(STMI-PC4-Pad33)") (class "Default")
      (node (ref "STM") (pin "33") (pinfunction "PC4_33") (pintype "bidirectional"))
    )
    (net (code "80") (name "unconnected-(STMI-PC5-Pad34)") (class "Default")
      (node (ref "STM") (pin "34") (pinfunction "PC5_34") (pintype "bidirectional"))
    )
    (net (code "81") (name "unconnected-(STMJ-PD11-Pad58)") (class "Default")
      (node (ref "STM") (pin "58") (pinfunction "PD11_58") (pintype "bidirectional"))
    )
    (net (code "82") (name "unconnected-(STMK-PD0-Pad81)") (class "Default")
      (node (ref "STM") (pin "81") (pinfunction "PD0_81") (pintype "bidirectional"))
    )
    (net (code "83") (name "unconnected-(STMK-PD1-Pad82)") (class "Default")
      (node (ref "STM") (pin "82") (pinfunction "PD1_82") (pintype "bidirectional"))
    )
    (net (code "84") (name "unconnected-(STMK-PD3-Pad84)") (class "Default")
      (node (ref "STM") (pin "84") (pinfunction "PD3_84") (pintype "bidirectional"))
    )
    (net (code "85") (name "unconnected-(STMK-PD4-Pad85)") (class "Default")
      (node (ref "STM") (pin "85") (pinfunction "PD4_85") (pintype "bidirectional"))
    )
    (net (code "86") (name "unconnected-(STMK-PD5-Pad86)") (class "Default")
      (node (ref "STM") (pin "86") (pinfunction "PD5_86") (pintype "bidirectional"))
    )
    (net (code "87") (name "unconnected-(STML-PE8-Pad39)") (class "Default")
      (node (ref "STM") (pin "39") (pinfunction "PE8_39") (pintype "bidirectional"))
    )
    (net (code "88") (name "unconnected-(STML-PE9-Pad40)") (class "Default")
      (node (ref "STM") (pin "40") (pinfunction "PE9_40") (pintype "bidirectional"))
    )
    (net (code "89") (name "unconnected-(STML-PE10-Pad41)") (class "Default")
      (node (ref "STM") (pin "41") (pinfunction "PE10_41") (pintype "bidirectional"))
    )
    (net (code "90") (name "unconnected-(STML-PE11-Pad42)") (class "Default")
      (node (ref "STM") (pin "42") (pinfunction "PE11_42") (pintype "bidirectional"))
    )
    (net (code "91") (name "unconnected-(STML-PE12-Pad43)") (class "Default")
      (node (ref "STM") (pin "43") (pinfunction "PE12_43") (pintype "bidirectional"))
    )
    (net (code "92") (name "unconnected-(STML-PE13-Pad44)") (class "Default")
      (node (ref "STM") (pin "44") (pinfunction "PE13_44") (pintype "bidirectional"))
    )
    (net (code "93") (name "unconnected-(STML-PE14-Pad45)") (class "Default")
      (node (ref "STM") (pin "45") (pinfunction "PE14_45") (pintype "bidirectional"))
    )
    (net (code "94") (name "unconnected-(STML-PE15-Pad46)") (class "Default")
      (node (ref "STM") (pin "46") (pinfunction "PE15_46") (pintype "bidirectional"))
    )
    (net (code "95") (name "unconnected-(STMM-PE0-Pad97)") (class "Default")
      (node (ref "STM") (pin "97") (pinfunction "PE0_97") (pintype "bidirectional"))
    )
    (net (code "96") (name "unconnected-(STMM-PE1-Pad98)") (class "Default")
      (node (ref "STM") (pin "98") (pinfunction "PE1_98") (pintype "bidirectional"))
    )
    (net (code "97") (name "unconnected-(STMM-PE2-Pad1)") (class "Default")
      (node (ref "STM") (pin "1") (pinfunction "PE2_1") (pintype "bidirectional"))
    )
    (net (code "98") (name "unconnected-(STMM-PE3-Pad2)") (class "Default")
      (node (ref "STM") (pin "2") (pinfunction "PE3_2") (pintype "bidirectional"))
    )
    (net (code "99") (name "unconnected-(STMM-PE4-Pad3)") (class "Default")
      (node (ref "STM") (pin "3") (pinfunction "PE4_3") (pintype "bidirectional"))
    )
    (net (code "100") (name "unconnected-(STMM-PE7-Pad38)") (class "Default")
      (node (ref "STM") (pin "38") (pinfunction "PE7_38") (pintype "bidirectional"))
    )
    (net (code "101") (name "unconnected-(U$1-VDD-Pad1)") (class "Default")
      (node (ref "U$1") (pin "1") (pinfunction "VDD_1") (pintype "bidirectional"))
    )
    (net (code "102") (name "unconnected-(U1-AIO0-Pad9)") (class "Default")
      (node (ref "U1") (pin "9") (pinfunction "AIO0_9") (pintype "bidirectional"))
    )
    (net (code "103") (name "unconnected-(U1-AIO1-Pad10)") (class "Default")
      (node (ref "U1") (pin "10") (pinfunction "AIO1_10") (pintype "bidirectional"))
    )
    (net (code "104") (name "unconnected-(U1-CLK-Pad19)") (class "Default")
      (node (ref "U1") (pin "19") (pinfunction "CLK_19") (pintype "bidirectional"))
    )
    (net (code "105") (name "unconnected-(U1-CSB-Pad16)") (class "Default")
      (node (ref "U1") (pin "16") (pinfunction "CSB_16") (pintype "bidirectional"))
    )
    (net (code "106") (name "unconnected-(U1-CTS-Pad3)") (class "Default")
      (node (ref "U1") (pin "3") (pinfunction "CTS_3") (pintype "bidirectional"))
    )
    (net (code "107") (name "unconnected-(U1-GND1-Pad21)") (class "Default")
      (node (ref "U1") (pin "21") (pinfunction "GND1_21") (pintype "bidirectional"))
    )
    (net (code "108") (name "unconnected-(U1-MISO-Pad18)") (class "Default")
      (node (ref "U1") (pin "18") (pinfunction "MISO_18") (pintype "bidirectional"))
    )
    (net (code "109") (name "unconnected-(U1-MOSI-Pad17)") (class "Default")
      (node (ref "U1") (pin "17") (pinfunction "MOSI_17") (pintype "bidirectional"))
    )
    (net (code "110") (name "unconnected-(U1-NC-Pad14)") (class "Default")
      (node (ref "U1") (pin "14") (pinfunction "NC_14") (pintype "bidirectional"))
    )
    (net (code "111") (name "unconnected-(U1-PCM_CLK-Pad5)") (class "Default")
      (node (ref "U1") (pin "5") (pinfunction "PCM_CLK_5") (pintype "bidirectional"))
    )
    (net (code "112") (name "unconnected-(U1-PCM_IN-Pad7)") (class "Default")
      (node (ref "U1") (pin "7") (pinfunction "PCM_IN_7") (pintype "bidirectional"))
    )
    (net (code "113") (name "unconnected-(U1-PCM_OUT-Pad6)") (class "Default")
      (node (ref "U1") (pin "6") (pinfunction "PCM_OUT_6") (pintype "bidirectional"))
    )
    (net (code "114") (name "unconnected-(U1-PCN_SYNC-Pad8)") (class "Default")
      (node (ref "U1") (pin "8") (pinfunction "PCN_SYNC_8") (pintype "bidirectional"))
    )
    (net (code "115") (name "unconnected-(U1-PIO0-Pad23)") (class "Default")
      (node (ref "U1") (pin "23") (pinfunction "PIO0_23") (pintype "bidirectional"))
    )
    (net (code "116") (name "unconnected-(U1-PIO1-Pad24)") (class "Default")
      (node (ref "U1") (pin "24") (pinfunction "PIO1_24") (pintype "bidirectional"))
    )
    (net (code "117") (name "unconnected-(U1-PIO2-Pad25)") (class "Default")
      (node (ref "U1") (pin "25") (pinfunction "PIO2_25") (pintype "bidirectional"))
    )
    (net (code "118") (name "unconnected-(U1-PIO3-Pad26)") (class "Default")
      (node (ref "U1") (pin "26") (pinfunction "PIO3_26") (pintype "bidirectional"))
    )
    (net (code "119") (name "unconnected-(U1-PIO4-Pad27)") (class "Default")
      (node (ref "U1") (pin "27") (pinfunction "PIO4_27") (pintype "bidirectional"))
    )
    (net (code "120") (name "unconnected-(U1-PIO5-Pad28)") (class "Default")
      (node (ref "U1") (pin "28") (pinfunction "PIO5_28") (pintype "bidirectional"))
    )
    (net (code "121") (name "unconnected-(U1-PIO6-Pad29)") (class "Default")
      (node (ref "U1") (pin "29") (pinfunction "PIO6_29") (pintype "bidirectional"))
    )
    (net (code "122") (name "unconnected-(U1-PIO7-Pad30)") (class "Default")
      (node (ref "U1") (pin "30") (pinfunction "PIO7_30") (pintype "bidirectional"))
    )
    (net (code "123") (name "unconnected-(U1-PIO9-Pad32)") (class "Default")
      (node (ref "U1") (pin "32") (pinfunction "PIO9_32") (pintype "bidirectional"))
    )
    (net (code "124") (name "unconnected-(U1-PIO10-Pad33)") (class "Default")
      (node (ref "U1") (pin "33") (pinfunction "PIO10_33") (pintype "bidirectional"))
    )
    (net (code "125") (name "unconnected-(U1-RST-Pad11)") (class "Default")
      (node (ref "U1") (pin "11") (pinfunction "RST_11") (pintype "bidirectional"))
    )
    (net (code "126") (name "unconnected-(U1-RTS-Pad4)") (class "Default")
      (node (ref "U1") (pin "4") (pinfunction "RTS_4") (pintype "bidirectional"))
    )
    (net (code "127") (name "unconnected-(U1-VBUSD+-Pad20)") (class "Default")
      (node (ref "U1") (pin "20") (pinfunction "VBUSD+_20") (pintype "bidirectional"))
    )
    (net (code "128") (name "unconnected-(U1-VBUSD--Pad15)") (class "Default")
      (node (ref "U1") (pin "15") (pinfunction "VBUSD-_15") (pintype "bidirectional"))
    )
  )
)
